# Power.net
KiCad netlist of a schematic drawn in Altium Designer
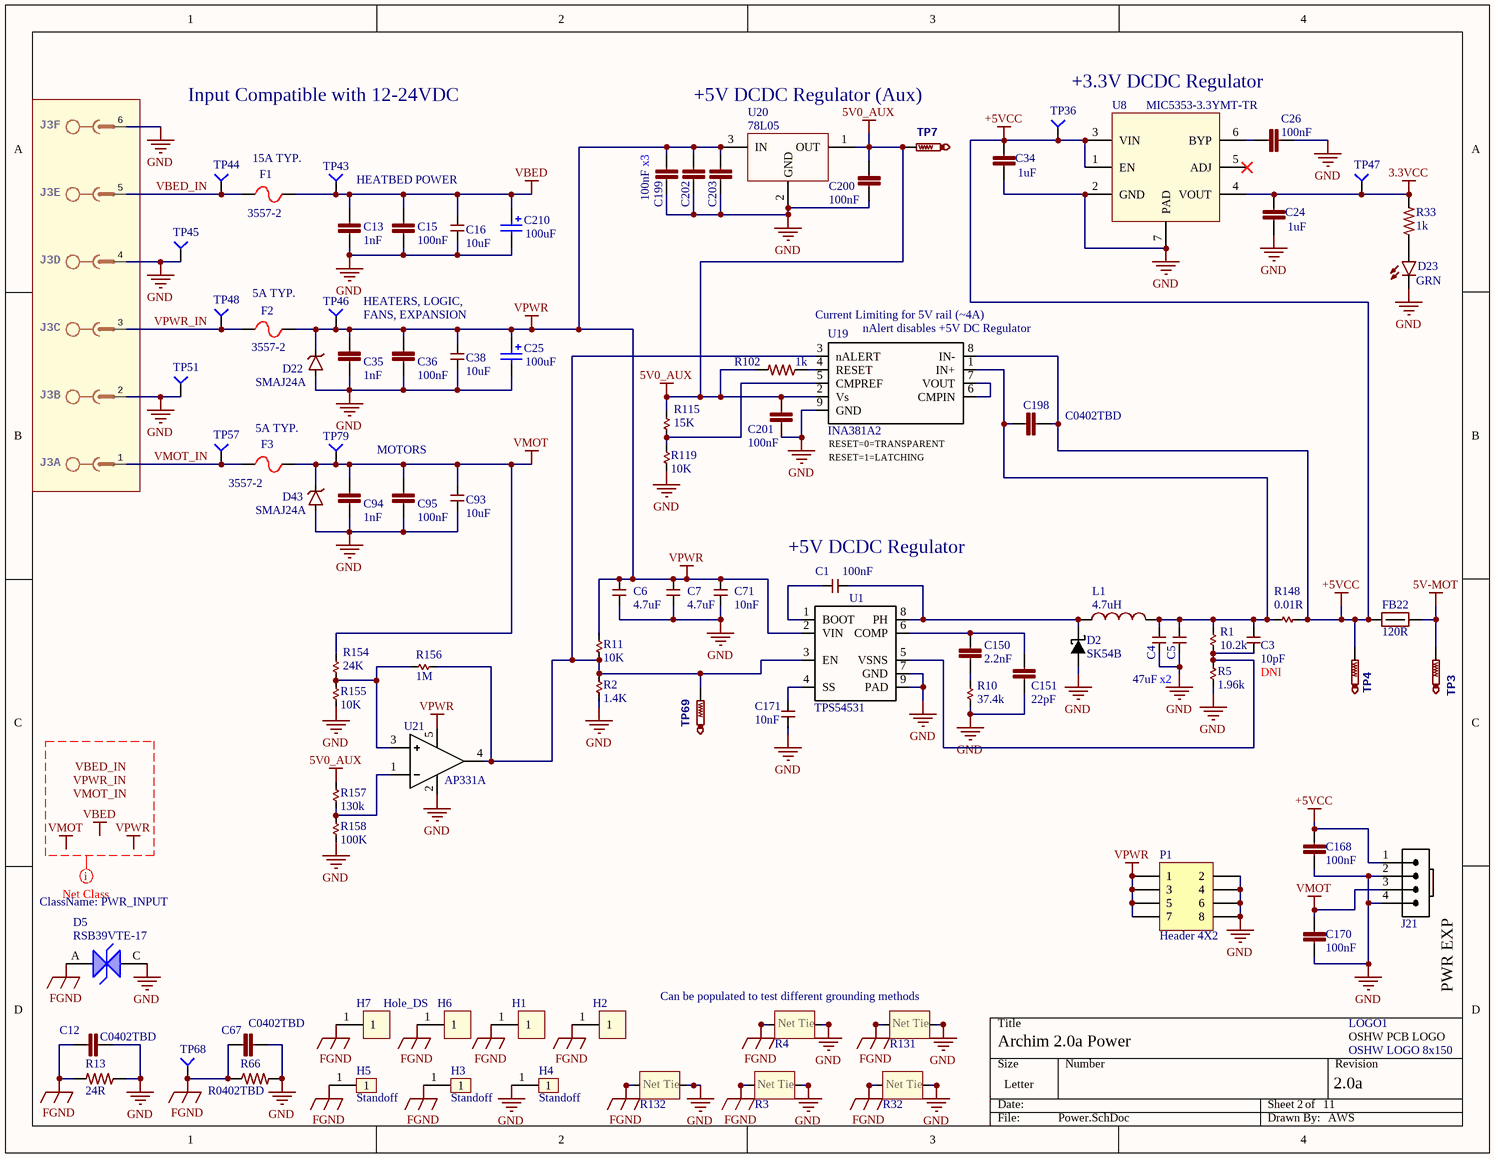
[diagram p0: Power.SchDoc]

(export (version "E")
  (design (tool "Eeschema 10.0.6"))
  (components
    (comp (ref "C1")
      (value "100nF")
      (footprint "C0603")
      (description "CAP CER 0603 100nF 50V 10% X7R")
      (fields (field (name "MANUFACTURER") "Kemet") (field (name "TOLERANCE") "+/- 10%"))
      (libsource (lib "Capacitors") (part "100nF 0603 50V X7R"))
    )
    (comp (ref "C3")
      (value "10pF")
      (footprint "C0402")
      (description "CAP CER 10PF 50V 5% NP0 0402")
      (fields
        (field (name "TOLERANCE") "5%")
        (field (name "MANUFACTURER") "Samsung")
        (field (name "DNI") "DNI")
      )
      (libsource (lib "Capacitors") (part "10pF 0402 50V NP0"))
    )
    (comp (ref "C4")
      (value "47uF")
      (footprint "C1210")
      (description "CAP CER 47UF 10V X5R 1210")
      (fields (field (name "MANUFACTURER") "Murata") (field (name "TOLERANCE") "10%"))
      (libsource (lib "Capacitors") (part "47uF 1210 10V X5R"))
    )
    (comp (ref "C5")
      (value "47uF")
      (footprint "C1210")
      (description "CAP CER 47UF 10V X5R 1210")
      (fields (field (name "MANUFACTURER") "Murata") (field (name "TOLERANCE") "10%"))
      (libsource (lib "Capacitors") (part "47uF 1210 10V X5R"))
    )
    (comp (ref "C6")
      (value "4.7uF")
      (footprint "C1210")
      (description "CAP CER 4.7UF 50V X7R 1210")
      (fields (field (name "MANUFACTURER") "Murata") (field (name "PART") "4.7uF 1210 50V X7R"))
      (libsource (lib "Capacitors") (part "4.7uF 1210 50V X7R"))
    )
    (comp (ref "C7")
      (value "4.7uF")
      (footprint "C1210")
      (description "CAP CER 4.7UF 50V X7R 1210")
      (fields (field (name "MANUFACTURER") "Murata") (field (name "PART") "4.7uF 1210 50V X7R"))
      (libsource (lib "Capacitors") (part "4.7uF 1210 50V X7R"))
    )
    (comp (ref "C12")
      (value "C0402TBD")
      (footprint "C0402")
      (description "Capacitor Non Polarized")
      (libsource (lib "3Delight") (part "C0402TBD"))
    )
    (comp (ref "C13")
      (value "1nF")
      (footprint "C0402")
      (description "1000pF 50V Ceramic Capacitor X7R 0402 (1005 Metric) 0.039\" L x 0.020\" W (1.00mm x 0.50mm)")
      (fields (field (name "MANUFACTURER") "Murata") (field (name "PART") "1nF 50V X7R 0402"))
      (libsource (lib "3Delight") (part "CAP 1nF 50V 0402 X7R"))
    )
    (comp (ref "C15")
      (value "100nF")
      (footprint "C0603")
      (description "CAP CER 0603 100nF 50V 10% X7R")
      (fields (field (name "MANUFACTURER") "Kemet") (field (name "PART") "100nF 50V X7R 0603"))
      (libsource (lib "3Delight") (part "C0603C104K5RACTU"))
    )
    (comp (ref "C16")
      (value "10uF")
      (footprint "C1206")
      (description "CAP CER 10UF 50V 10% X5R 1206")
      (fields (field (name "MANUFACTURER") "Murata") (field (name "PART") "CAP CER 10UF 50V X5R 1206"))
      (libsource (lib "Capacitors") (part "10uF 1206 50V X5R"))
    )
    (comp (ref "C24")
      (value "1uF")
      (footprint "C0402")
      (description "CAP CER 0402 1uF 6.3V 10% X5R")
      (fields (field (name "MANUFACTURER") "Murata") (field (name "PART") "1uF 6.3V X5R 0402"))
      (libsource (lib "3Delight") (part "GRM155R60J105KE19D"))
    )
    (comp (ref "C25")
      (value "100uF")
      (footprint "CAP-ELEC-063063077")
      (description "CAP ALUM 100UF 35V 20% SMD")
      (fields (field (name "MANUFACTURER") "Nichicon") (field (name "PART") "100uF 35V SMD Al-El"))
      (libsource (lib "3Delight") (part "UWT1V101MCL1GS"))
    )
    (comp (ref "C26")
      (value "100nF")
      (footprint "C0402")
      (description "CAP CER 0402 100nF 16V 10% X7R")
      (fields (field (name "MANUFACTURER") "Murata") (field (name "PART") "0.1uF 16V X7R 0402"))
      (libsource (lib "3Delight") (part "GRM155R71C104KA88D"))
    )
    (comp (ref "C34")
      (value "1uF")
      (footprint "C0402")
      (description "CAP CER 0402 1uF 6.3V 10% X5R")
      (fields (field (name "MANUFACTURER") "Murata") (field (name "PART") "1uF 6.3V X5R 0402"))
      (libsource (lib "3Delight") (part "GRM155R60J105KE19D"))
    )
    (comp (ref "C35")
      (value "1nF")
      (footprint "C0402")
      (description "1000pF 50V Ceramic Capacitor X7R 0402 (1005 Metric) 0.039\" L x 0.020\" W (1.00mm x 0.50mm)")
      (fields (field (name "MANUFACTURER") "Murata") (field (name "PART") "1nF 50V X7R 0402"))
      (libsource (lib "3Delight") (part "CAP 1nF 50V 0402 X7R"))
    )
    (comp (ref "C36")
      (value "100nF")
      (footprint "C0603")
      (description "CAP CER 0603 100nF 50V 10% X7R")
      (fields (field (name "MANUFACTURER") "Kemet") (field (name "PART") "100nF 50V X7R 0603"))
      (libsource (lib "3Delight") (part "C0603C104K5RACTU"))
    )
    (comp (ref "C38")
      (value "10uF")
      (footprint "C1206")
      (description "CAP CER 10UF 50V 10% X5R 1206")
      (fields (field (name "MANUFACTURER") "Murata") (field (name "PART") "CAP CER 10UF 50V X5R 1206"))
      (libsource (lib "Capacitors") (part "10uF 1206 50V X5R"))
    )
    (comp (ref "C67")
      (value "C0402TBD")
      (footprint "C0402")
      (description "Capacitor Non Polarized")
      (libsource (lib "3Delight") (part "C0402TBD"))
    )
    (comp (ref "C71")
      (value "10nF")
      (footprint "C0402")
      (description "CAP CER 10nF 50V X7R 0402")
      (fields (field (name "TOLERANCE") "5%") (field (name "MANUFACTURER") "Murata"))
      (libsource (lib "Capacitors") (part "10nF 0402 50V X7R"))
    )
    (comp (ref "C93")
      (value "10uF")
      (footprint "C1206")
      (description "CAP CER 10UF 50V 10% X5R 1206")
      (fields (field (name "MANUFACTURER") "Murata") (field (name "PART") "CAP CER 10UF 50V X5R 1206"))
      (libsource (lib "Capacitors") (part "10uF 1206 50V X5R"))
    )
    (comp (ref "C94")
      (value "1nF")
      (footprint "C0402")
      (description "1000pF 50V Ceramic Capacitor X7R 0402 (1005 Metric) 0.039\" L x 0.020\" W (1.00mm x 0.50mm)")
      (fields (field (name "MANUFACTURER") "Murata") (field (name "PART") "1nF 50V X7R 0402"))
      (libsource (lib "3Delight") (part "CAP 1nF 50V 0402 X7R"))
    )
    (comp (ref "C95")
      (value "100nF")
      (footprint "C0603")
      (description "CAP CER 0603 100nF 50V 10% X7R")
      (fields (field (name "MANUFACTURER") "Kemet") (field (name "PART") "100nF 50V X7R 0603"))
      (libsource (lib "3Delight") (part "C0603C104K5RACTU"))
    )
    (comp (ref "C150")
      (value "2.2nF")
      (footprint "C0402")
      (description "CAP CER 0402 2.2nF 25V C0G")
      (fields (field (name "MANUFACTURER") "Kemet") (field (name "PART") "2.2nF 25V C0G 0402"))
      (libsource (lib "Capacitors") (part "2.2nF 25V C0G 0402"))
    )
    (comp (ref "C151")
      (value "22pF")
      (footprint "C0402")
      (description "CAP CER 0402 22pF 50V 5% C0G")
      (fields (field (name "MANUFACTURER") "AVX") (field (name "PART") "22pF 50V"))
      (libsource (lib "Capacitors") (part "22pF 0402 50V C0G"))
    )
    (comp (ref "C168")
      (value "100nF")
      (footprint "C0402")
      (description "CAP CER 0402 100nF 16V 10% X7R")
      (fields (field (name "MANUFACTURER") "Murata") (field (name "PART") "0.1uF 16V X7R 0402"))
      (libsource (lib "3Delight") (part "GRM155R71C104KA88D"))
    )
    (comp (ref "C170")
      (value "100nF")
      (footprint "C0402")
      (description "CAP CER 0402 100nF 16V 10% X7R")
      (fields (field (name "MANUFACTURER") "Murata") (field (name "PART") "0.1uF 16V X7R 0402"))
      (libsource (lib "3Delight") (part "GRM155R71C104KA88D"))
    )
    (comp (ref "C171")
      (value "10nF")
      (footprint "C0402")
      (description "CAP CER 10nF 50V X7R 0402")
      (fields (field (name "TOLERANCE") "5%") (field (name "MANUFACTURER") "Murata"))
      (libsource (lib "Capacitors") (part "10nF 0402 50V X7R"))
    )
    (comp (ref "C198")
      (value "C0402TBD")
      (footprint "C0402")
      (description "Capacitor Non Polarized")
      (libsource (lib "Capacitors") (part "C0402TBD"))
    )
    (comp (ref "C199")
      (value "100nF")
      (footprint "C0603")
      (description "CAP CER 0603 100nF 50V 10% X7R")
      (fields (field (name "MANUFACTURER") "Kemet") (field (name "PART") "100nF 50V X7R 0603"))
      (libsource (lib "3Delight") (part "C0603C104K5RACTU"))
    )
    (comp (ref "C200")
      (value "100nF")
      (footprint "C0402")
      (description "CAP CER 0402 100nF 16V 10% X7R")
      (fields (field (name "MANUFACTURER") "Murata") (field (name "PART") "0.1uF 16V X7R 0402"))
      (libsource (lib "") (part "GRM155R71C104KA88D_1"))
    )
    (comp (ref "C201")
      (value "100nF")
      (footprint "C0402")
      (description "CAP CER 0402 100nF 16V 10% X7R")
      (fields (field (name "MANUFACTURER") "Murata") (field (name "PART") "0.1uF 16V X7R 0402"))
      (libsource (lib "") (part "GRM155R71C104KA88D_1"))
    )
    (comp (ref "C202")
      (value "100nF")
      (footprint "C0603")
      (description "CAP CER 0603 100nF 50V 10% X7R")
      (fields (field (name "MANUFACTURER") "Kemet") (field (name "PART") "100nF 50V X7R 0603"))
      (libsource (lib "3Delight") (part "C0603C104K5RACTU"))
    )
    (comp (ref "C203")
      (value "100nF")
      (footprint "C0603")
      (description "CAP CER 0603 100nF 50V 10% X7R")
      (fields (field (name "MANUFACTURER") "Kemet") (field (name "PART") "100nF 50V X7R 0603"))
      (libsource (lib "3Delight") (part "C0603C104K5RACTU"))
    )
    (comp (ref "C210")
      (value "100uF")
      (footprint "CAP-ELEC-063063077")
      (description "CAP ALUM 100UF 35V 20% SMD")
      (fields (field (name "MANUFACTURER") "Nichicon") (field (name "PART") "100uF 35V SMD Al-El"))
      (libsource (lib "3Delight") (part "UWT1V101MCL1GS"))
    )
    (comp (ref "D2")
      (value "SK54B")
      (footprint "SMB_DO-214AA_LRG")
      (description "DIODE SCHOTTKY 40V 5A SMB_DO214AA")
      (fields (field (name "MANUFACTURER") "MCC") (field (name "VOLTAGE") "40Vrb"))
      (libsource (lib "Diodes") (part "SK54B"))
    )
    (comp (ref "D5")
      (value "RSB39VTE-17")
      (footprint "SOD323-R")
      (description "DIODE TVS")
      (fields (field (name "MANUFACTURER") "Rohm") (field (name "PART") "TVS DIODE 30VWM SOD323"))
      (libsource (lib "3Delight") (part "RSB39VTE-17"))
    )
    (comp (ref "D22")
      (value "SMAJ24A")
      (footprint "SMA-SM")
      (description "TVS DIODE 24V 38.9V SMA")
      (fields (field (name "MANUFACTURER") "Bourns Inc"))
      (libsource (lib "Diodes") (part "SMAJ24A"))
    )
    (comp (ref "D23")
      (value "GRN")
      (footprint "LED2012120")
      (description "LED 0805 Green")
      (fields (field (name "MANUFACTURER") "Dialight") (field (name "PART") "LED GREEN CLEAR 0805 SMD"))
      (libsource (lib "LEDs") (part "5988170107F"))
    )
    (comp (ref "D43")
      (value "SMAJ24A")
      (footprint "SMA-SM")
      (description "TVS DIODE 24V 38.9V SMA")
      (fields (field (name "MANUFACTURER") "Bourns Inc"))
      (libsource (lib "Diodes") (part "SMAJ24A"))
    )
    (comp (ref "F1")
      (value "3557-2")
      (footprint "3557")
      (description "FUSE PTH ATO")
      (fields (field (name "MANUFACTURER") "Keystone") (field (name "PART") "Fuse Holder"))
      (libsource (lib "3Delight") (part "3557-2"))
    )
    (comp (ref "F2")
      (value "3557-2")
      (footprint "3557")
      (description "FUSE PTH ATO")
      (fields (field (name "MANUFACTURER") "Keystone") (field (name "PART") "Fuse Holder"))
      (libsource (lib "3Delight") (part "3557-2"))
    )
    (comp (ref "F3")
      (value "3557-2")
      (footprint "3557")
      (description "FUSE PTH ATO")
      (fields (field (name "MANUFACTURER") "Keystone") (field (name "PART") "Fuse Holder"))
      (libsource (lib "3Delight") (part "3557-2"))
    )
    (comp (ref "FB22")
      (value "120R")
      (footprint "FB0603")
      (description "FERRITE BEAD 120 OHM 0603 1LN")
      (fields (field (name "MANUFACTURER") "Samsung") (field (name "PART") "FERRITE 120R 3A 0603"))
      (libsource (lib "3Delight") (part "FERRITE 220R 2.5A 0603"))
    )
    (comp (ref "H1")
      (value "Hole_DS")
      (footprint "Wave_hole_3x7-doubleSided")
      (libsource (lib "Archim_0.4") (part "Hole_DS"))
    )
    (comp (ref "H2")
      (value "Hole_DS")
      (footprint "Wave_hole_3x7-doubleSided")
      (libsource (lib "Archim_0.4") (part "Hole_DS"))
    )
    (comp (ref "H3")
      (value "Standoff")
      (footprint "Standoff3mmTopConn")
      (description "Mechanical - Top connect")
      (libsource (lib "3Delight") (part "Standoff3TopConn"))
    )
    (comp (ref "H4")
      (value "Standoff")
      (footprint "Standoff3mmTopConn")
      (description "Mechanical - Top connect")
      (libsource (lib "3Delight") (part "Standoff3TopConn"))
    )
    (comp (ref "H5")
      (value "Standoff")
      (footprint "Standoff3mmTopConn")
      (description "Mechanical - Top connect")
      (libsource (lib "3Delight") (part "Standoff3TopConn"))
    )
    (comp (ref "H6")
      (value "Hole_DS")
      (footprint "Wave_hole_3x7-doubleSided")
      (libsource (lib "Archim_0.4") (part "Hole_DS"))
    )
    (comp (ref "H7")
      (value "Hole_DS")
      (footprint "Wave_hole_3x7-doubleSided")
      (libsource (lib "Archim_0.4") (part "Hole_DS"))
    )
    (comp (ref "J3")
      (value "MSTBH6")
      (footprint "MSTBH6")
      (description "PHOENIX")
      (fields (field (name "MANUFACTURER") "Molex") (field (name "PART") "6 Pin Conn RA"))
      (libsource (lib "3Delight") (part "MSTBH6"))
    )
    (comp (ref "J21")
      (value "Molex 0705430038")
      (footprint "4POL254 PIN-IN-PASTE")
      (description "Molex 4 Pin Clip Connector - Pin In Paste footprint")
      (libsource (lib "Connectors") (part "Molex 0705430003 PIP"))
    )
    (comp (ref "L1")
      (value "4.7uH")
      (footprint "IND_10X10")
      (description "FIXED IND 4.7UH 10A 15.5 MOHM")
      (fields (field (name "MANUFACTURER") "Bourns") (field (name "PART") "4.7uH 10A"))
      (libsource (lib "Inductors") (part "4.7uH 10A"))
    )
    (comp (ref "LOGO1")
      (value "OSHW LOGO 8x150")
      (footprint "OSHW_8X150_NOTEXT")
      (libsource (lib "MISC") (part "OSHW LOGO 8x150"))
    )
    (comp (ref "P1")
      (value "Header 4X2")
      (footprint "HDR2X4")
      (description "Header, 4-Pin, Dual row")
      (fields (field (name "MANUFACTURER") "Multicomp") (field (name "PART") "CONN 8Pin 2Row 0.1\""))
      (libsource (lib "Miscellaneous Connectors") (part "Header 4X2"))
    )
    (comp (ref "R1")
      (value "10.2k")
      (footprint "R0402")
      (description "RES SMD 10.2K OHM 1% 1/16W 0402")
      (fields (field (name "MANUFACTURER") "Yageo") (field (name "PART") "10.2k 1% 0402"))
      (libsource (lib "Resistors") (part "10.2k 1% 0402"))
    )
    (comp (ref "R2")
      (value "1.4K")
      (footprint "R0402")
      (description "RES SMD 1.4K OHM 1% 1/16W 0402")
      (fields (field (name "MANUFACTURER") "Stackpole") (field (name "TOLERANCE") "+/- 1%"))
      (libsource (lib "Resistors") (part "1.4k 1% 0402"))
    )
    (comp (ref "R3")
      (value "Net-Tie 0402")
      (footprint "Net Tie - R0402")
      (libsource (lib "MISC") (part "Net-Tie 0402"))
    )
    (comp (ref "R4")
      (value "Net-Tie 0402")
      (footprint "Net Tie - R0402")
      (libsource (lib "MISC") (part "Net-Tie 0402"))
    )
    (comp (ref "R5")
      (value "1.96k")
      (footprint "R0402")
      (description "RES SMD 1.96K OHM 1% 1/16W 0402")
      (fields (field (name "MANUFACTURER") "Yageo") (field (name "PART") "1.96k 1% 0402"))
      (libsource (lib "Resistors") (part "1.96k 1% 0402"))
    )
    (comp (ref "R10")
      (value "37.4k")
      (footprint "R0402")
      (description "RES SMD 37.4K OHM 1% 1/16W 0402")
      (fields (field (name "MANUFACTURER") "Yageo") (field (name "TOLERANCE") "1%"))
      (libsource (lib "Resistors") (part "37.4K 1% 0402"))
    )
    (comp (ref "R11")
      (value "10K")
      (footprint "R0402")
      (description "RES SMD 10K OHM 1% 1/16W 0402")
      (fields (field (name "MANUFACTURER") "Yageo") (field (name "PART") "10k 1% 0402"))
      (libsource (lib "Resistors") (part "10k 1% 0402"))
    )
    (comp (ref "R13")
      (value "24R")
      (footprint "R0402")
      (description "Res Thick Film 0402 24 Ohm 1% 0.063W")
      (fields (field (name "MANUFACTURER") "Yageo") (field (name "PART") "24R 1% 0402"))
      (libsource (lib "3Delight") (part "CRCW040224R0FKED"))
    )
    (comp (ref "R32")
      (value "Net-Tie 0402")
      (footprint "Net Tie - R0402")
      (libsource (lib "MISC") (part "Net-Tie 0402"))
    )
    (comp (ref "R33")
      (value "1k")
      (footprint "R0402")
      (description "RES 0402 1k 63mW 1%")
      (fields (field (name "MANUFACTURER") "Yageo") (field (name "PART") "1k 1% 0402"))
      (libsource (lib "3Delight") (part "RK73H1ETTP1001F"))
    )
    (comp (ref "R66")
      (value "R0402TBD")
      (footprint "R0402")
      (description "Resistor")
      (libsource (lib "3Delight") (part "R0402TBD"))
    )
    (comp (ref "R102")
      (value "1k")
      (footprint "R0402")
      (description "RES 0402 1k 63mW 1%")
      (fields (field (name "MANUFACTURER") "Yageo") (field (name "PART") "1k 1% 0402"))
      (libsource (lib "3Delight") (part "RK73H1ETTP1001F"))
    )
    (comp (ref "R115")
      (value "15K")
      (footprint "R0402")
      (description "RES SMD 15K 1% 1/16W 0402")
      (fields (field (name "MANUFACTURER") "Samsung") (field (name "PART") "15K 1% 0402"))
      (libsource (lib "Resistors") (part "15K 1% 0402"))
    )
    (comp (ref "R119")
      (value "10K")
      (footprint "R0402")
      (description "RES SMD 10K OHM 1% 1/16W 0402")
      (fields (field (name "MANUFACTURER") "Yageo") (field (name "PART") "10k 1% 0402"))
      (libsource (lib "Resistors") (part "10k 1% 0402"))
    )
    (comp (ref "R131")
      (value "Net-Tie 0402")
      (footprint "Net Tie - R0402")
      (libsource (lib "MISC") (part "Net-Tie 0402"))
    )
    (comp (ref "R132")
      (value "Net-Tie 0402")
      (footprint "Net Tie - R0402")
      (libsource (lib "MISC") (part "Net-Tie 0402"))
    )
    (comp (ref "R148")
      (value "0.01R")
      (footprint "R0805")
      (description "RES 0.01 OHM 1% 1/2W 0805")
      (fields (field (name "MANUFACTURER") "Susumu") (field (name "PART") "0.01 1% 0.5W 0805"))
      (libsource (lib "Resistors") (part "0.01R 1% 0805"))
    )
    (comp (ref "R154")
      (value "24K")
      (footprint "R0402")
      (description "RES SMD 24K OHM 1% 1/16W 0402")
      (fields (field (name "MANUFACTURER") "Visha Dale") (field (name "TOLERANCE") "+/- 1%"))
      (libsource (lib "Resistors") (part "24k 1% 0402"))
    )
    (comp (ref "R155")
      (value "10K")
      (footprint "R0402")
      (description "RES SMD 10K OHM 1% 1/16W 0402")
      (fields (field (name "MANUFACTURER") "Yageo") (field (name "PART") "10k 1% 0402"))
      (libsource (lib "Resistors") (part "10k 1% 0402"))
    )
    (comp (ref "R156")
      (value "1M")
      (footprint "Passives:R0402")
      (description "RES 0402 1M 100mW 5%")
      (fields (field (name "MANUFACTURER") "Panasonic") (field (name "PART") "1M 5% 0402"))
      (libsource (lib "Resistors") (part "1M 5% 0402"))
    )
    (comp (ref "R157")
      (value "130k")
      (footprint "Passives:R0402")
      (description "RES SMD 130K OHM 5% 1/16W 0402")
      (fields (field (name "MANUFACTURER") "Yageo") (field (name "PART") "130k 1% 0402"))
      (libsource (lib "Resistors") (part "130k 1% 0402"))
    )
    (comp (ref "R158")
      (value "100K")
      (footprint "Passives:R0402")
      (description "RES SMD 100K OHM 1% 1/16W 0402")
      (fields (field (name "MANUFACTURER") "Samsung") (field (name "PART") "100k 1% 0402"))
      (libsource (lib "Resistors") (part "100k 1% 0402"))
    )
    (comp (ref "TP3")
      (value "TestPoint")
      (footprint "TP1-27")
      (description "Test Point")
      (libsource (lib "3Delight") (part "TestPoint"))
    )
    (comp (ref "TP4")
      (value "TestPoint")
      (footprint "TP1-27")
      (description "Test Point")
      (libsource (lib "3Delight") (part "TestPoint"))
    )
    (comp (ref "TP7")
      (value "TestPoint")
      (footprint "TP1-27")
      (description "Test Point")
      (libsource (lib "") (part "TestPoint_1"))
    )
    (comp (ref "TP36")
      (value "TP4")
      (footprint "TP-2")
      (description "Socket")
      (libsource (lib "Archim") (part "Socket"))
    )
    (comp (ref "TP43")
      (value "TP4")
      (footprint "TP-2")
      (description "Socket")
      (libsource (lib "Archim") (part "Socket"))
    )
    (comp (ref "TP44")
      (value "TP4")
      (footprint "TP-2")
      (description "Socket")
      (libsource (lib "Archim") (part "Socket"))
    )
    (comp (ref "TP45")
      (value "TP4")
      (footprint "TP-2")
      (description "Socket")
      (libsource (lib "Archim") (part "Socket"))
    )
    (comp (ref "TP46")
      (value "TP4")
      (footprint "TP-2")
      (description "Socket")
      (libsource (lib "Archim") (part "Socket"))
    )
    (comp (ref "TP47")
      (value "TP4")
      (footprint "TP-2")
      (description "Socket")
      (libsource (lib "Archim") (part "Socket"))
    )
    (comp (ref "TP48")
      (value "TP4")
      (footprint "TP-2")
      (description "Socket")
      (libsource (lib "Archim") (part "Socket"))
    )
    (comp (ref "TP51")
      (value "TP4")
      (footprint "TP-2")
      (description "Socket")
      (libsource (lib "Archim") (part "Socket"))
    )
    (comp (ref "TP57")
      (value "TP4")
      (footprint "TP-2")
      (description "Socket")
      (libsource (lib "Archim") (part "Socket"))
    )
    (comp (ref "TP68")
      (value "TP4")
      (footprint "TP-2")
      (description "Socket")
      (libsource (lib "Archim") (part "Socket"))
    )
    (comp (ref "TP69")
      (value "TestPoint")
      (footprint "TP1-27")
      (description "Test Point")
      (libsource (lib "3Delight") (part "TestPoint"))
    )
    (comp (ref "TP79")
      (value "TP4")
      (footprint "TP-2")
      (description "Socket")
      (libsource (lib "Archim") (part "Socket"))
    )
    (comp (ref "U1")
      (value "TPS54531")
      (footprint "SOIC127P600X170_HS-9L")
      (description "IC REG BUCK ADJ 5A 8SOPWRPAD")
      (fields (field (name "MANUFACTURER") "TI"))
      (libsource (lib "ICs-Power") (part "TPS54531"))
    )
    (comp (ref "U8")
      (value "MIC5353-3.3YMT-TR")
      (footprint "TDFN1616-6LD-PL-1")
      (description "LDO 3.3V 500mA - low ESR Cout")
      (fields (field (name "MANUFACTURER") "Microchip") (field (name "PART") "IC REG LDO 3.3V 0.5A 6TMLF"))
      (libsource (lib "Tigershark3D") (part "MIC5353-3.3YMT-TR"))
    )
    (comp (ref "U19")
      (value "INA381A2")
      (footprint "WSON8_2x2mm")
      (description "IC COMPARATOR BIDIR 8WSON")
      (fields (field (name "MANUFACTURER") "TI") (field (name "TOLERANCE") "-NA-"))
      (libsource (lib "ICs-Analog") (part "INA381_ALT"))
    )
    (comp (ref "U20")
      (value "78L05")
      (footprint "SOT-89-3")
      (description "IC REG LINEAR 5V 100MA SOT89-3")
      (fields (field (name "MANUFACTURER") "ST") (field (name "TOLERANCE") "-NA-"))
      (libsource (lib "ICs-Power") (part "78L05"))
    )
    (comp (ref "U21")
      (value "AP331A")
      (footprint "SOT23-5")
      (description "IC QUAD DIFF COMPARATOR 14 -SOIC")
      (fields (field (name "MANUFACTURER") "TEXAS INSTRUMENTS"))
      (libsource (lib "ICs-Analog") (part "AP331A"))
    )
  )
  (nets
    (net (code "1") (name "+5VCC") (class "Default")
      (node (ref "C168") (pin "2") (pinfunction "2_2") (pintype "passive"))
      (node (ref "C198") (pin "1") (pinfunction "1_1") (pintype "passive"))
      (node (ref "C34") (pin "1") (pinfunction "1_1") (pintype "passive"))
      (node (ref "FB22") (pin "1") (pinfunction "1_1") (pintype "passive"))
      (node (ref "J21") (pin "1") (pinfunction "1_1") (pintype "passive"))
      (node (ref "R148") (pin "2") (pinfunction "2_2") (pintype "passive"))
      (node (ref "TP36") (pin "1") (pinfunction "1_1") (pintype "passive"))
      (node (ref "TP4") (pin "TP") (pinfunction "TP_TP") (pintype "passive"))
      (node (ref "U19") (pin "8") (pinfunction "IN-_8") (pintype "power_in"))
      (node (ref "U8") (pin "1") (pinfunction "EN_1") (pintype "power_in"))
      (node (ref "U8") (pin "3") (pinfunction "VIN_3") (pintype "power_in"))
    )
    (net (code "2") (name "/VBED_IN") (class "Default")
      (node (ref "F1") (pin "1") (pinfunction "1_1") (pintype "passive"))
      (node (ref "J3") (pin "5") (pinfunction "5_5") (pintype "passive"))
      (node (ref "TP44") (pin "1") (pinfunction "1_1") (pintype "passive"))
    )
    (net (code "3") (name "/VMOT_IN") (class "Default")
      (node (ref "F3") (pin "1") (pinfunction "1_1") (pintype "passive"))
      (node (ref "J3") (pin "1") (pinfunction "1_1") (pintype "passive"))
      (node (ref "TP57") (pin "1") (pinfunction "1_1") (pintype "passive"))
    )
    (net (code "4") (name "/VPWR_IN") (class "Default")
      (node (ref "F2") (pin "1") (pinfunction "1_1") (pintype "passive"))
      (node (ref "J3") (pin "3") (pinfunction "1_3") (pintype "passive"))
      (node (ref "TP48") (pin "1") (pinfunction "1_1") (pintype "passive"))
    )
    (net (code "5") (name "3.3VCC") (class "Default")
      (node (ref "C24") (pin "1") (pinfunction "1_1") (pintype "passive"))
      (node (ref "R33") (pin "2") (pinfunction "2_2") (pintype "passive"))
      (node (ref "TP47") (pin "1") (pinfunction "1_1") (pintype "passive"))
      (node (ref "U8") (pin "4") (pinfunction "VOUT_4") (pintype "power_in"))
    )
    (net (code "6") (name "5V-MOT") (class "Default")
      (node (ref "FB22") (pin "2") (pinfunction "2_2") (pintype "passive"))
      (node (ref "TP3") (pin "TP") (pinfunction "TP_TP") (pintype "passive"))
    )
    (net (code "7") (name "5V0_AUX") (class "Default")
      (node (ref "C200") (pin "2") (pinfunction "2_2") (pintype "passive"))
      (node (ref "C201") (pin "2") (pinfunction "2_2") (pintype "passive"))
      (node (ref "R102") (pin "2") (pinfunction "2_2") (pintype "passive"))
      (node (ref "R115") (pin "2") (pinfunction "2_2") (pintype "passive"))
      (node (ref "R157") (pin "2") (pinfunction "2_2") (pintype "passive"))
      (node (ref "TP7") (pin "TP") (pinfunction "TP_TP") (pintype "passive"))
      (node (ref "U19") (pin "2") (pinfunction "Vs_2") (pintype "power_in"))
      (node (ref "U20") (pin "1") (pinfunction "OUT_1") (pintype "power_in"))
    )
    (net (code "8") (name "FGND") (class "Default")
      (node (ref "C12") (pin "1") (pinfunction "1_1") (pintype "passive"))
      (node (ref "C67") (pin "1") (pinfunction "1_1") (pintype "passive"))
      (node (ref "D5") (pin "A") (pinfunction "A_A") (pintype "power_in"))
      (node (ref "H1") (pin "1") (pinfunction "1_1") (pintype "power_in"))
      (node (ref "H2") (pin "1") (pinfunction "1_1") (pintype "power_in"))
      (node (ref "H3") (pin "1") (pinfunction "1_1") (pintype "power_in"))
      (node (ref "H5") (pin "1") (pinfunction "1_1") (pintype "power_in"))
      (node (ref "H6") (pin "1") (pinfunction "1_1") (pintype "power_in"))
      (node (ref "H7") (pin "1") (pinfunction "1_1") (pintype "power_in"))
      (node (ref "R13") (pin "2") (pinfunction "2_2") (pintype "passive"))
      (node (ref "R131") (pin "1") (pinfunction "1_1") (pintype "power_in"))
      (node (ref "R132") (pin "1") (pinfunction "1_1") (pintype "power_in"))
      (node (ref "R3") (pin "1") (pinfunction "1_1") (pintype "power_in"))
      (node (ref "R32") (pin "1") (pinfunction "1_1") (pintype "power_in"))
      (node (ref "R4") (pin "1") (pinfunction "1_1") (pintype "power_in"))
      (node (ref "R66") (pin "1") (pinfunction "1_1") (pintype "passive"))
      (node (ref "TP68") (pin "1") (pinfunction "1_1") (pintype "passive"))
    )
    (net (code "9") (name "GND") (class "Default")
      (node (ref "C12") (pin "2") (pinfunction "2_2") (pintype "passive"))
      (node (ref "C13") (pin "2") (pinfunction "2_2") (pintype "passive"))
      (node (ref "C15") (pin "2") (pinfunction "2_2") (pintype "passive"))
      (node (ref "C151") (pin "1") (pinfunction "1_1") (pintype "passive"))
      (node (ref "C16") (pin "1") (pinfunction "1_1") (pintype "passive"))
      (node (ref "C168") (pin "1") (pinfunction "1_1") (pintype "passive"))
      (node (ref "C170") (pin "1") (pinfunction "1_1") (pintype "passive"))
      (node (ref "C171") (pin "1") (pinfunction "1_1") (pintype "passive"))
      (node (ref "C199") (pin "2") (pinfunction "2_2") (pintype "passive"))
      (node (ref "C200") (pin "1") (pinfunction "1_1") (pintype "passive"))
      (node (ref "C201") (pin "1") (pinfunction "1_1") (pintype "passive"))
      (node (ref "C202") (pin "2") (pinfunction "2_2") (pintype "passive"))
      (node (ref "C203") (pin "2") (pinfunction "2_2") (pintype "passive"))
      (node (ref "C210") (pin "2") (pinfunction "2_2") (pintype "passive"))
      (node (ref "C24") (pin "2") (pinfunction "2_2") (pintype "passive"))
      (node (ref "C25") (pin "2") (pinfunction "2_2") (pintype "passive"))
      (node (ref "C26") (pin "2") (pinfunction "2_2") (pintype "passive"))
      (node (ref "C34") (pin "2") (pinfunction "2_2") (pintype "passive"))
      (node (ref "C35") (pin "2") (pinfunction "2_2") (pintype "passive"))
      (node (ref "C36") (pin "2") (pinfunction "2_2") (pintype "passive"))
      (node (ref "C38") (pin "1") (pinfunction "1_1") (pintype "passive"))
      (node (ref "C4") (pin "1") (pinfunction "1_1") (pintype "passive"))
      (node (ref "C5") (pin "1") (pinfunction "1_1") (pintype "passive"))
      (node (ref "C6") (pin "1") (pinfunction "1_1") (pintype "passive"))
      (node (ref "C67") (pin "2") (pinfunction "2_2") (pintype "passive"))
      (node (ref "C7") (pin "1") (pinfunction "1_1") (pintype "passive"))
      (node (ref "C71") (pin "1") (pinfunction "1_1") (pintype "passive"))
      (node (ref "C93") (pin "1") (pinfunction "1_1") (pintype "passive"))
      (node (ref "C94") (pin "2") (pinfunction "2_2") (pintype "passive"))
      (node (ref "C95") (pin "2") (pinfunction "2_2") (pintype "passive"))
      (node (ref "D2") (pin "A") (pinfunction "ANODE_A") (pintype "passive"))
      (node (ref "D22") (pin "A") (pinfunction "A_A") (pintype "passive"))
      (node (ref "D23") (pin "C") (pinfunction "C_C") (pintype "passive"))
      (node (ref "D43") (pin "A") (pinfunction "A_A") (pintype "passive"))
      (node (ref "D5") (pin "C") (pinfunction "C_C") (pintype "power_in"))
      (node (ref "H4") (pin "1") (pinfunction "1_1") (pintype "power_in"))
      (node (ref "J21") (pin "2") (pinfunction "2_2") (pintype "passive"))
      (node (ref "J21") (pin "4") (pinfunction "4_4") (pintype "passive"))
      (node (ref "J3") (pin "2") (pinfunction "1_2") (pintype "passive"))
      (node (ref "J3") (pin "4") (pinfunction "1_4") (pintype "passive"))
      (node (ref "J3") (pin "6") (pinfunction "6_6") (pintype "passive"))
      (node (ref "P1") (pin "2") (pinfunction "2_2") (pintype "passive"))
      (node (ref "P1") (pin "4") (pinfunction "4_4") (pintype "passive"))
      (node (ref "P1") (pin "6") (pinfunction "6_6") (pintype "passive"))
      (node (ref "P1") (pin "8") (pinfunction "8_8") (pintype "passive"))
      (node (ref "R10") (pin "1") (pinfunction "1_1") (pintype "passive"))
      (node (ref "R119") (pin "1") (pinfunction "1_1") (pintype "passive"))
      (node (ref "R13") (pin "1") (pinfunction "1_1") (pintype "passive"))
      (node (ref "R131") (pin "2") (pinfunction "2_2") (pintype "power_in"))
      (node (ref "R132") (pin "2") (pinfunction "2_2") (pintype "power_in"))
      (node (ref "R155") (pin "1") (pinfunction "1_1") (pintype "passive"))
      (node (ref "R158") (pin "1") (pinfunction "1_1") (pintype "passive"))
      (node (ref "R2") (pin "1") (pinfunction "1_1") (pintype "passive"))
      (node (ref "R3") (pin "2") (pinfunction "2_2") (pintype "power_in"))
      (node (ref "R32") (pin "2") (pinfunction "2_2") (pintype "power_in"))
      (node (ref "R4") (pin "2") (pinfunction "2_2") (pintype "power_in"))
      (node (ref "R5") (pin "1") (pinfunction "1_1") (pintype "passive"))
      (node (ref "R66") (pin "2") (pinfunction "2_2") (pintype "passive"))
      (node (ref "TP45") (pin "1") (pinfunction "1_1") (pintype "passive"))
      (node (ref "TP51") (pin "1") (pinfunction "1_1") (pintype "passive"))
      (node (ref "U1") (pin "7") (pinfunction "GND_7") (pintype "passive"))
      (node (ref "U1") (pin "9") (pinfunction "PAD_9") (pintype "passive"))
      (node (ref "U19") (pin "9") (pinfunction "GND_9") (pintype "power_in"))
      (node (ref "U20") (pin "2") (pinfunction "GND_2") (pintype "power_in"))
      (node (ref "U21") (pin "2") (pinfunction "GND_2") (pintype "power_in"))
      (node (ref "U8") (pin "2") (pinfunction "GND_2") (pintype "power_in"))
      (node (ref "U8") (pin "7") (pinfunction "PAD_7") (pintype "power_in"))
    )
    (net (code "10") (name "Net-(C150-Pad1)") (class "Default")
      (node (ref "C150") (pin "1") (pinfunction "1_1") (pintype "passive"))
      (node (ref "R10") (pin "2") (pinfunction "2_2") (pintype "passive"))
    )
    (net (code "11") (name "Net-(D2-CATHODE)") (class "Default")
      (node (ref "C1") (pin "2") (pinfunction "2_2") (pintype "passive"))
      (node (ref "D2") (pin "K") (pinfunction "CATHODE_K") (pintype "passive"))
      (node (ref "L1") (pin "1") (pinfunction "1_1") (pintype "passive"))
      (node (ref "U1") (pin "8") (pinfunction "PH_8") (pintype "passive"))
    )
    (net (code "12") (name "Net-(D23-PadA)") (class "Default")
      (node (ref "D23") (pin "A") (pinfunction "A_A") (pintype "passive"))
      (node (ref "R33") (pin "1") (pinfunction "1_1") (pintype "passive"))
    )
    (net (code "13") (name "Net-(U1-BOOT)") (class "Default")
      (node (ref "C1") (pin "1") (pinfunction "1_1") (pintype "passive"))
      (node (ref "U1") (pin "1") (pinfunction "BOOT_1") (pintype "passive"))
    )
    (net (code "14") (name "Net-(U1-COMP)") (class "Default")
      (node (ref "C150") (pin "2") (pinfunction "2_2") (pintype "passive"))
      (node (ref "C151") (pin "2") (pinfunction "2_2") (pintype "passive"))
      (node (ref "U1") (pin "6") (pinfunction "COMP_6") (pintype "passive"))
    )
    (net (code "15") (name "Net-(U1-EN)") (class "Default")
      (node (ref "R11") (pin "1") (pinfunction "1_1") (pintype "passive"))
      (node (ref "R156") (pin "1") (pinfunction "1_1") (pintype "passive"))
      (node (ref "R2") (pin "2") (pinfunction "2_2") (pintype "passive"))
      (node (ref "TP69") (pin "TP") (pinfunction "TP_TP") (pintype "passive"))
      (node (ref "U1") (pin "3") (pinfunction "EN_3") (pintype "passive"))
      (node (ref "U19") (pin "3") (pinfunction "nALERT_3") (pintype "power_in"))
      (node (ref "U21") (pin "4") (pinfunction "OUT_4") (pintype "passive"))
    )
    (net (code "16") (name "Net-(U1-SS)") (class "Default")
      (node (ref "C171") (pin "2") (pinfunction "2_2") (pintype "passive"))
      (node (ref "U1") (pin "4") (pinfunction "SS_4") (pintype "passive"))
    )
    (net (code "17") (name "Net-(U1-VSNS)") (class "Default")
      (node (ref "C3") (pin "1") (pinfunction "1_1") (pintype "passive"))
      (node (ref "R1") (pin "2") (pinfunction "2_2") (pintype "passive"))
      (node (ref "R5") (pin "2") (pinfunction "2_2") (pintype "passive"))
      (node (ref "U1") (pin "5") (pinfunction "VSNS_5") (pintype "passive"))
    )
    (net (code "18") (name "Net-(U8-BYP)") (class "Default")
      (node (ref "C26") (pin "1") (pinfunction "1_1") (pintype "passive"))
      (node (ref "U8") (pin "6") (pinfunction "BYP_6") (pintype "power_in"))
    )
    (net (code "19") (name "Net-(U19-CMPIN)") (class "Default")
      (node (ref "U19") (pin "6") (pinfunction "CMPIN_6") (pintype "power_in"))
      (node (ref "U19") (pin "7") (pinfunction "VOUT_7") (pintype "power_in"))
    )
    (net (code "20") (name "Net-(U19-CMPREF)") (class "Default")
      (node (ref "R115") (pin "1") (pinfunction "1_1") (pintype "passive"))
      (node (ref "R119") (pin "2") (pinfunction "2_2") (pintype "passive"))
      (node (ref "U19") (pin "5") (pinfunction "CMPREF_5") (pintype "power_in"))
    )
    (net (code "21") (name "Net-(U19-IN+)") (class "Default")
      (node (ref "C198") (pin "2") (pinfunction "2_2") (pintype "passive"))
      (node (ref "C3") (pin "2") (pinfunction "2_2") (pintype "passive"))
      (node (ref "C4") (pin "2") (pinfunction "2_2") (pintype "passive"))
      (node (ref "C5") (pin "2") (pinfunction "2_2") (pintype "passive"))
      (node (ref "L1") (pin "2") (pinfunction "2_2") (pintype "passive"))
      (node (ref "R1") (pin "1") (pinfunction "1_1") (pintype "passive"))
      (node (ref "R148") (pin "1") (pinfunction "1_1") (pintype "passive"))
      (node (ref "U19") (pin "1") (pinfunction "IN+_1") (pintype "power_in"))
    )
    (net (code "22") (name "Net-(U19-RESET)") (class "Default")
      (node (ref "R102") (pin "1") (pinfunction "1_1") (pintype "passive"))
      (node (ref "U19") (pin "4") (pinfunction "RESET_4") (pintype "power_in"))
    )
    (net (code "23") (name "Net-(U21-IN+)") (class "Default")
      (node (ref "R154") (pin "2") (pinfunction "2_2") (pintype "passive"))
      (node (ref "R155") (pin "2") (pinfunction "2_2") (pintype "passive"))
      (node (ref "R156") (pin "2") (pinfunction "2_2") (pintype "passive"))
      (node (ref "U21") (pin "3") (pinfunction "IN+_3") (pintype "passive"))
    )
    (net (code "24") (name "Net-(U21-IN-)") (class "Default")
      (node (ref "R157") (pin "1") (pinfunction "1_1") (pintype "passive"))
      (node (ref "R158") (pin "2") (pinfunction "2_2") (pintype "passive"))
      (node (ref "U21") (pin "1") (pinfunction "IN-_1") (pintype "passive"))
    )
    (net (code "25") (name "VBED") (class "Default")
      (node (ref "C13") (pin "1") (pinfunction "1_1") (pintype "passive"))
      (node (ref "C15") (pin "1") (pinfunction "1_1") (pintype "passive"))
      (node (ref "C16") (pin "2") (pinfunction "2_2") (pintype "passive"))
      (node (ref "C210") (pin "1") (pinfunction "1_1") (pintype "passive"))
      (node (ref "F1") (pin "2") (pinfunction "2_2") (pintype "passive"))
      (node (ref "TP43") (pin "1") (pinfunction "1_1") (pintype "passive"))
    )
    (net (code "26") (name "VMOT") (class "Default")
      (node (ref "C170") (pin "2") (pinfunction "2_2") (pintype "passive"))
      (node (ref "C93") (pin "2") (pinfunction "2_2") (pintype "passive"))
      (node (ref "C94") (pin "1") (pinfunction "1_1") (pintype "passive"))
      (node (ref "C95") (pin "1") (pinfunction "1_1") (pintype "passive"))
      (node (ref "D43") (pin "K") (pinfunction "K_K") (pintype "passive"))
      (node (ref "F3") (pin "2") (pinfunction "2_2") (pintype "passive"))
      (node (ref "J21") (pin "3") (pinfunction "3_3") (pintype "passive"))
      (node (ref "R154") (pin "1") (pinfunction "1_1") (pintype "passive"))
      (node (ref "TP79") (pin "1") (pinfunction "1_1") (pintype "passive"))
    )
    (net (code "27") (name "VPWR") (class "Default")
      (node (ref "C199") (pin "1") (pinfunction "1_1") (pintype "passive"))
      (node (ref "C202") (pin "1") (pinfunction "1_1") (pintype "passive"))
      (node (ref "C203") (pin "1") (pinfunction "1_1") (pintype "passive"))
      (node (ref "C25") (pin "1") (pinfunction "1_1") (pintype "passive"))
      (node (ref "C35") (pin "1") (pinfunction "1_1") (pintype "passive"))
      (node (ref "C36") (pin "1") (pinfunction "1_1") (pintype "passive"))
      (node (ref "C38") (pin "2") (pinfunction "2_2") (pintype "passive"))
      (node (ref "C6") (pin "2") (pinfunction "2_2") (pintype "passive"))
      (node (ref "C7") (pin "2") (pinfunction "2_2") (pintype "passive"))
      (node (ref "C71") (pin "2") (pinfunction "2_2") (pintype "passive"))
      (node (ref "D22") (pin "K") (pinfunction "K_K") (pintype "passive"))
      (node (ref "F2") (pin "2") (pinfunction "2_2") (pintype "passive"))
      (node (ref "P1") (pin "1") (pinfunction "1_1") (pintype "passive"))
      (node (ref "P1") (pin "3") (pinfunction "3_3") (pintype "passive"))
      (node (ref "P1") (pin "5") (pinfunction "5_5") (pintype "passive"))
      (node (ref "P1") (pin "7") (pinfunction "7_7") (pintype "passive"))
      (node (ref "R11") (pin "2") (pinfunction "2_2") (pintype "passive"))
      (node (ref "TP46") (pin "1") (pinfunction "1_1") (pintype "passive"))
      (node (ref "U1") (pin "2") (pinfunction "VIN_2") (pintype "passive"))
      (node (ref "U20") (pin "3") (pinfunction "IN_3") (pintype "power_in"))
      (node (ref "U21") (pin "5") (pinfunction "VCC_5") (pintype "power_in"))
    )
    (net (code "28") (name "unconnected-(U8-ADJ-Pad5)") (class "Default")
      (node (ref "U8") (pin "5") (pinfunction "ADJ_5") (pintype "power_in+no_connect"))
    )
  )
)
